# W5500_2.net
KiCad netlist of a schematic drawn in Altium Designer
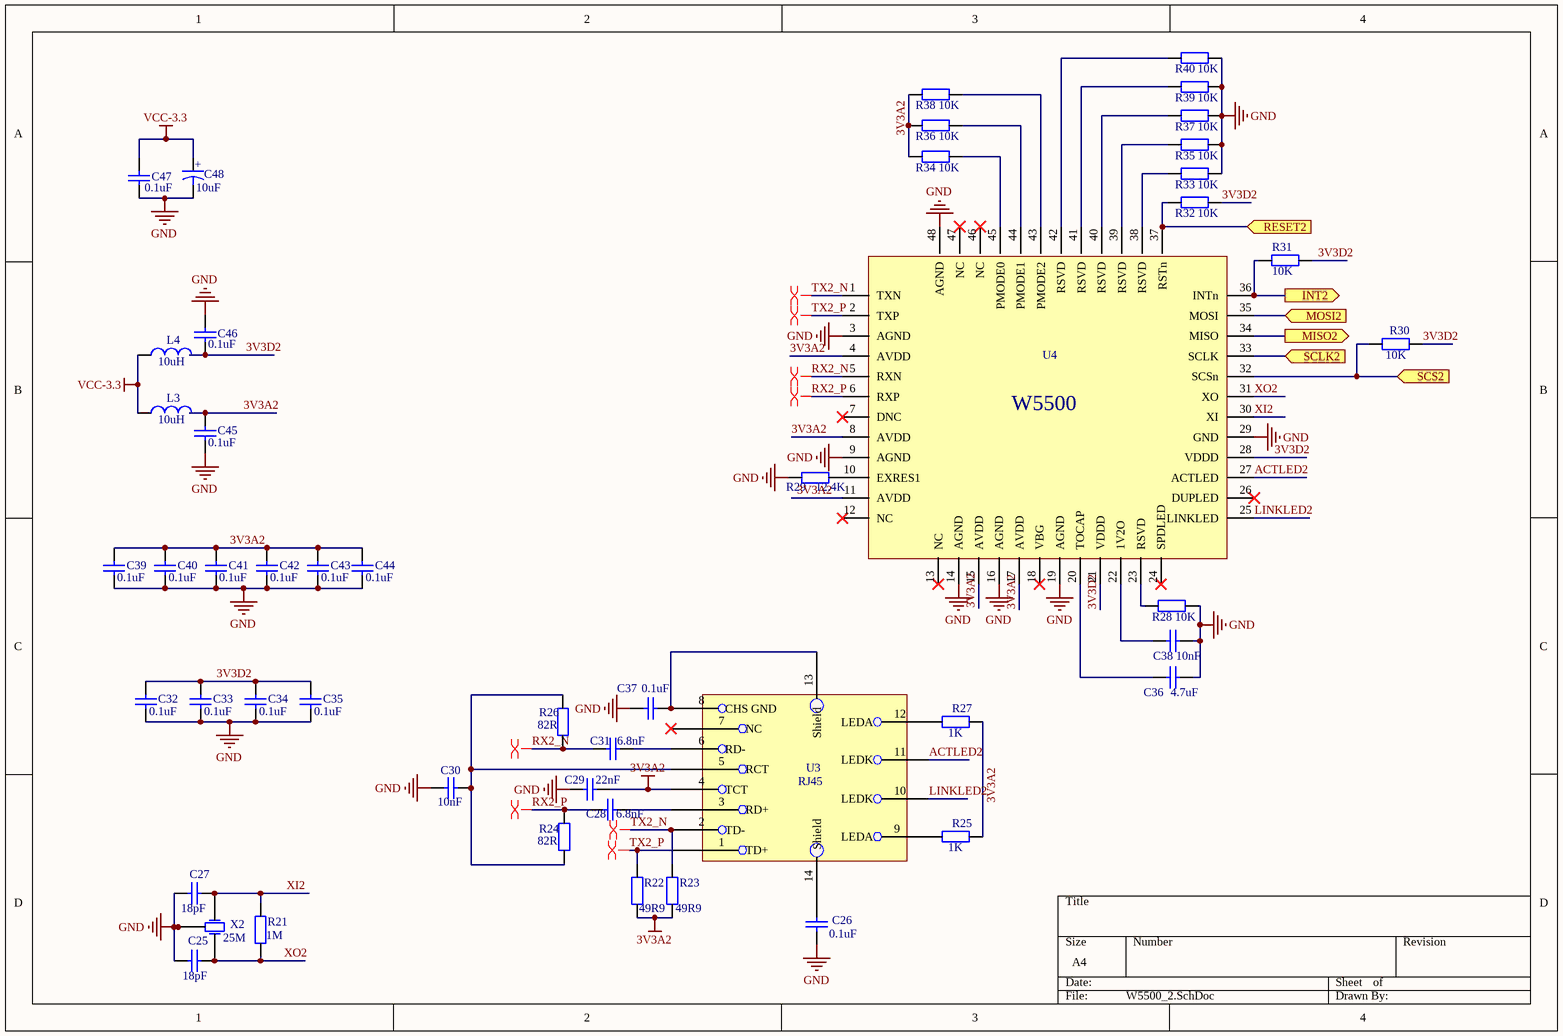
[diagram p0: W5500_2.SchDoc]

(export (version "E")
  (design (tool "Eeschema 10.0.6"))
  (components
    (comp (ref "C25")
      (value "18pF")
      (footprint "0603")
      (fields (field (name "Comment") "Capacitor-0603"))
      (libsource (lib "原理图库") (part "Capacitor-0603"))
    )
    (comp (ref "C26")
      (value "0.1uF")
      (footprint "0603")
      (fields (field (name "Comment") "Capacitor-0603"))
      (libsource (lib "原理图库") (part "Capacitor-0603"))
    )
    (comp (ref "C27")
      (value "18pF")
      (footprint "0603")
      (fields (field (name "Comment") "Capacitor-0603"))
      (libsource (lib "原理图库") (part "Capacitor-0603"))
    )
    (comp (ref "C28")
      (value "6.8nF")
      (footprint "0603")
      (fields (field (name "Comment") "Capacitor-0603"))
      (libsource (lib "原理图库") (part "Capacitor-0603"))
    )
    (comp (ref "C29")
      (value "22nF")
      (footprint "0603")
      (fields (field (name "Comment") "Capacitor-0603"))
      (libsource (lib "原理图库") (part "Capacitor-0603"))
    )
    (comp (ref "C30")
      (value "10nF")
      (footprint "0603")
      (fields (field (name "Comment") "Capacitor-0603"))
      (libsource (lib "原理图库") (part "Capacitor-0603"))
    )
    (comp (ref "C31")
      (value "6.8nF")
      (footprint "0603")
      (fields (field (name "Comment") "Capacitor-0603"))
      (libsource (lib "原理图库") (part "Capacitor-0603"))
    )
    (comp (ref "C32")
      (value "0.1uF")
      (footprint "0603")
      (fields (field (name "Comment") "Capacitor-0603"))
      (libsource (lib "原理图库") (part "Capacitor-0603"))
    )
    (comp (ref "C33")
      (value "0.1uF")
      (footprint "0603")
      (fields (field (name "Comment") "Capacitor-0603"))
      (libsource (lib "原理图库") (part "Capacitor-0603"))
    )
    (comp (ref "C34")
      (value "0.1uF")
      (footprint "0603")
      (fields (field (name "Comment") "Capacitor-0603"))
      (libsource (lib "原理图库") (part "Capacitor-0603"))
    )
    (comp (ref "C35")
      (value "0.1uF")
      (footprint "0603")
      (fields (field (name "Comment") "Capacitor-0603"))
      (libsource (lib "原理图库") (part "Capacitor-0603"))
    )
    (comp (ref "C36")
      (value "4.7uF")
      (footprint "0603")
      (fields (field (name "Comment") "Capacitor-0805"))
      (libsource (lib "原理图库") (part "Capacitor-0805"))
    )
    (comp (ref "C37")
      (value "0.1uF")
      (footprint "0603")
      (fields (field (name "Comment") "Capacitor-0603"))
      (libsource (lib "原理图库") (part "Capacitor-0603"))
    )
    (comp (ref "C38")
      (value "10nF")
      (footprint "0603")
      (fields (field (name "Comment") "Capacitor-0603"))
      (libsource (lib "原理图库") (part "Capacitor-0603"))
    )
    (comp (ref "C39")
      (value "0.1uF")
      (footprint "0603")
      (fields (field (name "Comment") "Capacitor-0603"))
      (libsource (lib "原理图库") (part "Capacitor-0603"))
    )
    (comp (ref "C40")
      (value "0.1uF")
      (footprint "0603")
      (fields (field (name "Comment") "Capacitor-0603"))
      (libsource (lib "原理图库") (part "Capacitor-0603"))
    )
    (comp (ref "C41")
      (value "0.1uF")
      (footprint "0603")
      (fields (field (name "Comment") "Capacitor-0603"))
      (libsource (lib "原理图库") (part "Capacitor-0603"))
    )
    (comp (ref "C42")
      (value "0.1uF")
      (footprint "0603")
      (fields (field (name "Comment") "Capacitor-0603"))
      (libsource (lib "原理图库") (part "Capacitor-0603"))
    )
    (comp (ref "C43")
      (value "0.1uF")
      (footprint "0603")
      (fields (field (name "Comment") "Capacitor-0603"))
      (libsource (lib "原理图库") (part "Capacitor-0603"))
    )
    (comp (ref "C44")
      (value "0.1uF")
      (footprint "0603")
      (fields (field (name "Comment") "Capacitor-0603"))
      (libsource (lib "原理图库") (part "Capacitor-0603"))
    )
    (comp (ref "C45")
      (value "0.1uF")
      (footprint "0603")
      (fields (field (name "Comment") "Capacitor-0603"))
      (libsource (lib "原理图库") (part "Capacitor-0603"))
    )
    (comp (ref "C46")
      (value "0.1uF")
      (footprint "0603")
      (fields (field (name "Comment") "Capacitor-0603"))
      (libsource (lib "原理图库") (part "Capacitor-0603"))
    )
    (comp (ref "C47")
      (value "0.1uF")
      (footprint "0603")
      (fields (field (name "Comment") "Capacitor-0603"))
      (libsource (lib "原理图库") (part "Capacitor-0603"))
    )
    (comp (ref "C48")
      (value "10uF")
      (footprint "钽电容1206（A3216）")
      (fields (field (name "ALTIUM_UNNAMED_1") "+") (field (name "Comment") "电解电容"))
      (libsource (lib "原理图库") (part "电解电容"))
    )
    (comp (ref "L3")
      (value "10uH")
      (footprint "0805")
      (fields (field (name "Comment") "Inductor"))
      (libsource (lib "原理图库") (part "Inductor"))
    )
    (comp (ref "L4")
      (value "10uH")
      (footprint "0805")
      (fields (field (name "Comment") "Inductor"))
      (libsource (lib "原理图库") (part "Inductor"))
    )
    (comp (ref "R21")
      (value "1M")
      (footprint "0603")
      (fields (field (name "Comment") "Resistor-0603"))
      (libsource (lib "") (part "Resistor-0603_1"))
    )
    (comp (ref "R22")
      (value "49R9")
      (footprint "0603")
      (fields (field (name "Comment") "Resistor-0603"))
      (libsource (lib "") (part "Resistor-0603_1"))
    )
    (comp (ref "R23")
      (value "49R9")
      (footprint "0603")
      (fields (field (name "Comment") "Resistor-0603"))
      (libsource (lib "") (part "Resistor-0603_1"))
    )
    (comp (ref "R24")
      (value "82R")
      (footprint "0603")
      (fields (field (name "Comment") "Resistor-0603"))
      (libsource (lib "") (part "Resistor-0603_1"))
    )
    (comp (ref "R25")
      (value "1K")
      (footprint "0603")
      (fields (field (name "Comment") "Resistor-0603"))
      (libsource (lib "") (part "Resistor-0603_2"))
    )
    (comp (ref "R26")
      (value "82R")
      (footprint "0603")
      (fields (field (name "Comment") "Resistor-0603"))
      (libsource (lib "") (part "Resistor-0603_1"))
    )
    (comp (ref "R27")
      (value "1K")
      (footprint "0603")
      (fields (field (name "Comment") "Resistor-0603"))
      (libsource (lib "") (part "Resistor-0603_2"))
    )
    (comp (ref "R28")
      (value "10K")
      (footprint "0603")
      (fields (field (name "Comment") "Resistor-0603"))
      (libsource (lib "原理图库") (part "Resistor-0603"))
    )
    (comp (ref "R29")
      (value "12.4K")
      (footprint "0603")
      (fields (field (name "Comment") "Resistor-0603"))
      (libsource (lib "原理图库") (part "Resistor-0603"))
    )
    (comp (ref "R30")
      (value "10K")
      (footprint "0603")
      (fields (field (name "Comment") "Resistor-0603"))
      (libsource (lib "") (part "Resistor-0603_2"))
    )
    (comp (ref "R31")
      (value "10K")
      (footprint "0603")
      (fields (field (name "Comment") "Resistor-0603"))
      (libsource (lib "") (part "Resistor-0603_2"))
    )
    (comp (ref "R32")
      (value "10K")
      (footprint "0603")
      (fields (field (name "Comment") "Resistor-0603"))
      (libsource (lib "原理图库") (part "Resistor-0603"))
    )
    (comp (ref "R33")
      (value "10K")
      (footprint "0603")
      (fields (field (name "Comment") "Resistor-0603"))
      (libsource (lib "原理图库") (part "Resistor-0603"))
    )
    (comp (ref "R34")
      (value "10K")
      (footprint "0603")
      (fields (field (name "Comment") "Resistor-0603"))
      (libsource (lib "原理图库") (part "Resistor-0603"))
    )
    (comp (ref "R35")
      (value "10K")
      (footprint "0603")
      (fields (field (name "Comment") "Resistor-0603"))
      (libsource (lib "原理图库") (part "Resistor-0603"))
    )
    (comp (ref "R36")
      (value "10K")
      (footprint "0603")
      (fields (field (name "Comment") "Resistor-0603"))
      (libsource (lib "原理图库") (part "Resistor-0603"))
    )
    (comp (ref "R37")
      (value "10K")
      (footprint "0603")
      (fields (field (name "Comment") "Resistor-0603"))
      (libsource (lib "原理图库") (part "Resistor-0603"))
    )
    (comp (ref "R38")
      (value "10K")
      (footprint "0603")
      (fields (field (name "Comment") "Resistor-0603"))
      (libsource (lib "原理图库") (part "Resistor-0603"))
    )
    (comp (ref "R39")
      (value "10K")
      (footprint "0603")
      (fields (field (name "Comment") "Resistor-0603"))
      (libsource (lib "原理图库") (part "Resistor-0603"))
    )
    (comp (ref "R40")
      (value "10K")
      (footprint "0603")
      (fields (field (name "Comment") "Resistor-0603"))
      (libsource (lib "原理图库") (part "Resistor-0603"))
    )
    (comp (ref "U3")
      (value "RJ45")
      (footprint "RJ45")
      (fields (field (name "NAME") "RJ45"))
      (libsource (lib "原理图库") (part "RJ45"))
    )
    (comp (ref "U4") (value "W5500") (footprint "W5500") (libsource (lib "原理图库") (part "W5500")))
    (comp (ref "X2")
      (value "25M")
      (footprint "3225无源晶振")
      (fields (field (name "Comment") "3225无源晶振"))
      (libsource (lib "原理图库") (part "3225无源晶振"))
    )
  )
  (nets
    (net (code "1") (name "/3V3D2") (class "Default")
      (node (ref "C32") (pin "1") (pinfunction "1_1") (pintype "passive"))
      (node (ref "C33") (pin "1") (pinfunction "1_1") (pintype "passive"))
      (node (ref "C34") (pin "1") (pinfunction "1_1") (pintype "passive"))
      (node (ref "C35") (pin "1") (pinfunction "1_1") (pintype "passive"))
      (node (ref "C46") (pin "1") (pinfunction "1_1") (pintype "passive"))
      (node (ref "L4") (pin "2") (pinfunction "2_2") (pintype "passive"))
      (node (ref "R30") (pin "2") (pinfunction "2_2") (pintype "passive"))
      (node (ref "R31") (pin "2") (pinfunction "2_2") (pintype "passive"))
      (node (ref "R32") (pin "1") (pinfunction "1_1") (pintype "passive"))
      (node (ref "U4") (pin "21") (pinfunction "VDDD_21") (pintype "passive"))
      (node (ref "U4") (pin "28") (pinfunction "VDDD_28") (pintype "passive"))
    )
    (net (code "2") (name "/ACTLED2") (class "Default")
      (node (ref "U3") (pin "11") (pinfunction "LEDK_11") (pintype "passive"))
      (node (ref "U4") (pin "27") (pinfunction "ACTLED_27") (pintype "passive"))
    )
    (net (code "3") (name "/INT2") (class "Default")
      (node (ref "R31") (pin "1") (pinfunction "1_1") (pintype "passive"))
      (node (ref "U4") (pin "36") (pinfunction "INTn_36") (pintype "passive"))
    )
    (net (code "4") (name "/LINKLED2") (class "Default")
      (node (ref "U3") (pin "10") (pinfunction "LEDK_10") (pintype "passive"))
      (node (ref "U4") (pin "25") (pinfunction "LINKLED_25") (pintype "passive"))
    )
    (net (code "5") (name "/MISO2") (class "Default")
      (node (ref "U4") (pin "34") (pinfunction "MISO_34") (pintype "passive"))
    )
    (net (code "6") (name "/MOSI2") (class "Default")
      (node (ref "U4") (pin "35") (pinfunction "MOSI_35") (pintype "passive"))
    )
    (net (code "7") (name "/RESET2") (class "Default")
      (node (ref "R32") (pin "2") (pinfunction "2_2") (pintype "passive"))
      (node (ref "U4") (pin "37") (pinfunction "RSTn_37") (pintype "passive"))
    )
    (net (code "8") (name "/RX2_N") (class "Default")
      (node (ref "C31") (pin "1") (pinfunction "1_1") (pintype "passive"))
      (node (ref "R26") (pin "2") (pinfunction "2_2") (pintype "passive"))
      (node (ref "U4") (pin "5") (pinfunction "RXN_5") (pintype "passive"))
    )
    (net (code "9") (name "/RX2_P") (class "Default")
      (node (ref "C28") (pin "1") (pinfunction "1_1") (pintype "passive"))
      (node (ref "R24") (pin "1") (pinfunction "1_1") (pintype "passive"))
      (node (ref "U4") (pin "6") (pinfunction "RXP_6") (pintype "passive"))
    )
    (net (code "10") (name "/SCLK2") (class "Default")
      (node (ref "U4") (pin "33") (pinfunction "SCLK_33") (pintype "passive"))
    )
    (net (code "11") (name "/SCS2") (class "Default")
      (node (ref "R30") (pin "1") (pinfunction "1_1") (pintype "passive"))
      (node (ref "U4") (pin "32") (pinfunction "SCSn_32") (pintype "passive"))
    )
    (net (code "12") (name "/TX2_N") (class "Default")
      (node (ref "R23") (pin "1") (pinfunction "1_1") (pintype "passive"))
      (node (ref "U3") (pin "2") (pinfunction "TD-_2") (pintype "passive"))
      (node (ref "U4") (pin "1") (pinfunction "TXN_1") (pintype "passive"))
    )
    (net (code "13") (name "/TX2_P") (class "Default")
      (node (ref "R22") (pin "1") (pinfunction "1_1") (pintype "passive"))
      (node (ref "U3") (pin "1") (pinfunction "TD+_1") (pintype "passive"))
      (node (ref "U4") (pin "2") (pinfunction "TXP_2") (pintype "passive"))
    )
    (net (code "14") (name "/XI2") (class "Default")
      (node (ref "C27") (pin "2") (pinfunction "2_2") (pintype "passive"))
      (node (ref "R21") (pin "1") (pinfunction "1_1") (pintype "passive"))
      (node (ref "U4") (pin "30") (pinfunction "XI_30") (pintype "passive"))
      (node (ref "X2") (pin "1") (pinfunction "OSC1_1") (pintype "passive"))
    )
    (net (code "15") (name "/XO2") (class "Default")
      (node (ref "C25") (pin "2") (pinfunction "2_2") (pintype "passive"))
      (node (ref "R21") (pin "2") (pinfunction "2_2") (pintype "passive"))
      (node (ref "U4") (pin "31") (pinfunction "XO_31") (pintype "passive"))
      (node (ref "X2") (pin "3") (pinfunction "OSC2_3") (pintype "passive"))
    )
    (net (code "16") (name "3V3A2") (class "Default")
      (node (ref "C29") (pin "2") (pinfunction "2_2") (pintype "passive"))
      (node (ref "C39") (pin "1") (pinfunction "1_1") (pintype "passive"))
      (node (ref "C40") (pin "1") (pinfunction "1_1") (pintype "passive"))
      (node (ref "C41") (pin "1") (pinfunction "1_1") (pintype "passive"))
      (node (ref "C42") (pin "1") (pinfunction "1_1") (pintype "passive"))
      (node (ref "C43") (pin "1") (pinfunction "1_1") (pintype "passive"))
      (node (ref "C44") (pin "1") (pinfunction "1_1") (pintype "passive"))
      (node (ref "C45") (pin "1") (pinfunction "1_1") (pintype "passive"))
      (node (ref "L3") (pin "2") (pinfunction "2_2") (pintype "passive"))
      (node (ref "R22") (pin "2") (pinfunction "2_2") (pintype "passive"))
      (node (ref "R23") (pin "2") (pinfunction "2_2") (pintype "passive"))
      (node (ref "R25") (pin "2") (pinfunction "2_2") (pintype "passive"))
      (node (ref "R27") (pin "2") (pinfunction "2_2") (pintype "passive"))
      (node (ref "R34") (pin "2") (pinfunction "2_2") (pintype "passive"))
      (node (ref "R36") (pin "2") (pinfunction "2_2") (pintype "passive"))
      (node (ref "R38") (pin "2") (pinfunction "2_2") (pintype "passive"))
      (node (ref "U3") (pin "4") (pinfunction "TCT_4") (pintype "passive"))
      (node (ref "U4") (pin "11") (pinfunction "AVDD_11") (pintype "passive"))
      (node (ref "U4") (pin "15") (pinfunction "AVDD_15") (pintype "passive"))
      (node (ref "U4") (pin "17") (pinfunction "AVDD_17") (pintype "passive"))
      (node (ref "U4") (pin "4") (pinfunction "AVDD_4") (pintype "passive"))
      (node (ref "U4") (pin "8") (pinfunction "AVDD_8") (pintype "passive"))
    )
    (net (code "17") (name "GND") (class "Default")
      (node (ref "C25") (pin "1") (pinfunction "1_1") (pintype "passive"))
      (node (ref "C26") (pin "2") (pinfunction "2_2") (pintype "passive"))
      (node (ref "C27") (pin "1") (pinfunction "1_1") (pintype "passive"))
      (node (ref "C29") (pin "1") (pinfunction "1_1") (pintype "passive"))
      (node (ref "C30") (pin "1") (pinfunction "1_1") (pintype "passive"))
      (node (ref "C32") (pin "2") (pinfunction "2_2") (pintype "passive"))
      (node (ref "C33") (pin "2") (pinfunction "2_2") (pintype "passive"))
      (node (ref "C34") (pin "2") (pinfunction "2_2") (pintype "passive"))
      (node (ref "C35") (pin "2") (pinfunction "2_2") (pintype "passive"))
      (node (ref "C36") (pin "2") (pinfunction "2_2") (pintype "passive"))
      (node (ref "C37") (pin "2") (pinfunction "2_2") (pintype "passive"))
      (node (ref "C38") (pin "1") (pinfunction "1_1") (pintype "passive"))
      (node (ref "C39") (pin "2") (pinfunction "2_2") (pintype "passive"))
      (node (ref "C40") (pin "2") (pinfunction "2_2") (pintype "passive"))
      (node (ref "C41") (pin "2") (pinfunction "2_2") (pintype "passive"))
      (node (ref "C42") (pin "2") (pinfunction "2_2") (pintype "passive"))
      (node (ref "C43") (pin "2") (pinfunction "2_2") (pintype "passive"))
      (node (ref "C44") (pin "2") (pinfunction "2_2") (pintype "passive"))
      (node (ref "C45") (pin "2") (pinfunction "2_2") (pintype "passive"))
      (node (ref "C46") (pin "2") (pinfunction "2_2") (pintype "passive"))
      (node (ref "C47") (pin "1") (pinfunction "1_1") (pintype "passive"))
      (node (ref "C48") (pin "1") (pinfunction "1_1") (pintype "passive"))
      (node (ref "R28") (pin "1") (pinfunction "1_1") (pintype "passive"))
      (node (ref "R29") (pin "2") (pinfunction "2_2") (pintype "passive"))
      (node (ref "R33") (pin "1") (pinfunction "1_1") (pintype "passive"))
      (node (ref "R35") (pin "1") (pinfunction "1_1") (pintype "passive"))
      (node (ref "R37") (pin "1") (pinfunction "1_1") (pintype "passive"))
      (node (ref "R39") (pin "1") (pinfunction "1_1") (pintype "passive"))
      (node (ref "R40") (pin "1") (pinfunction "1_1") (pintype "passive"))
      (node (ref "U4") (pin "14") (pinfunction "AGND_14") (pintype "passive"))
      (node (ref "U4") (pin "16") (pinfunction "AGND_16") (pintype "passive"))
      (node (ref "U4") (pin "19") (pinfunction "AGND_19") (pintype "passive"))
      (node (ref "U4") (pin "29") (pinfunction "GND_29") (pintype "passive"))
      (node (ref "U4") (pin "3") (pinfunction "AGND_3") (pintype "passive"))
      (node (ref "U4") (pin "48") (pinfunction "AGND_48") (pintype "passive"))
      (node (ref "U4") (pin "9") (pinfunction "AGND_9") (pintype "passive"))
      (node (ref "X2") (pin "2") (pinfunction "GND_2") (pintype "passive"))
      (node (ref "X2") (pin "4") (pinfunction "GND_4") (pintype "passive"))
    )
    (net (code "18") (name "Net-(C26-Pad1)") (class "Default")
      (node (ref "C26") (pin "1") (pinfunction "1_1") (pintype "passive"))
      (node (ref "U3") (pin "14") (pinfunction "Shield_14") (pintype "passive"))
    )
    (net (code "19") (name "Net-(R25-Pad1)") (class "Default")
      (node (ref "R25") (pin "1") (pinfunction "1_1") (pintype "passive"))
      (node (ref "U3") (pin "9") (pinfunction "LEDA_9") (pintype "passive"))
    )
    (net (code "20") (name "Net-(R27-Pad1)") (class "Default")
      (node (ref "R27") (pin "1") (pinfunction "1_1") (pintype "passive"))
      (node (ref "U3") (pin "12") (pinfunction "LEDA_12") (pintype "passive"))
    )
    (net (code "21") (name "Net-(R28-Pad2)") (class "Default")
      (node (ref "R28") (pin "2") (pinfunction "2_2") (pintype "passive"))
      (node (ref "U4") (pin "23") (pinfunction "RSVD_23") (pintype "passive"))
    )
    (net (code "22") (name "Net-(R33-Pad2)") (class "Default")
      (node (ref "R33") (pin "2") (pinfunction "2_2") (pintype "passive"))
      (node (ref "U4") (pin "38") (pinfunction "RSVD_38") (pintype "passive"))
    )
    (net (code "23") (name "Net-(R35-Pad2)") (class "Default")
      (node (ref "R35") (pin "2") (pinfunction "2_2") (pintype "passive"))
      (node (ref "U4") (pin "39") (pinfunction "RSVD_39") (pintype "passive"))
    )
    (net (code "24") (name "Net-(R37-Pad2)") (class "Default")
      (node (ref "R37") (pin "2") (pinfunction "2_2") (pintype "passive"))
      (node (ref "U4") (pin "40") (pinfunction "RSVD_40") (pintype "passive"))
    )
    (net (code "25") (name "Net-(R39-Pad2)") (class "Default")
      (node (ref "R39") (pin "2") (pinfunction "2_2") (pintype "passive"))
      (node (ref "U4") (pin "41") (pinfunction "RSVD_41") (pintype "passive"))
    )
    (net (code "26") (name "Net-(R40-Pad2)") (class "Default")
      (node (ref "R40") (pin "2") (pinfunction "2_2") (pintype "passive"))
      (node (ref "U4") (pin "42") (pinfunction "RSVD_42") (pintype "passive"))
    )
    (net (code "27") (name "Net-(U3-CHS_GND)") (class "Default")
      (node (ref "C37") (pin "1") (pinfunction "1_1") (pintype "passive"))
      (node (ref "U3") (pin "13") (pinfunction "Shield_13") (pintype "passive"))
      (node (ref "U3") (pin "8") (pinfunction "CHS_GND_8") (pintype "passive"))
    )
    (net (code "28") (name "Net-(U3-RCT)") (class "Default")
      (node (ref "C30") (pin "2") (pinfunction "2_2") (pintype "passive"))
      (node (ref "R24") (pin "2") (pinfunction "2_2") (pintype "passive"))
      (node (ref "R26") (pin "1") (pinfunction "1_1") (pintype "passive"))
      (node (ref "U3") (pin "5") (pinfunction "RCT_5") (pintype "passive"))
    )
    (net (code "29") (name "Net-(U3-RD+)") (class "Default")
      (node (ref "C28") (pin "2") (pinfunction "2_2") (pintype "passive"))
      (node (ref "U3") (pin "3") (pinfunction "RD+_3") (pintype "passive"))
    )
    (net (code "30") (name "Net-(U3-RD-)") (class "Default")
      (node (ref "C31") (pin "2") (pinfunction "2_2") (pintype "passive"))
      (node (ref "U3") (pin "6") (pinfunction "RD-_6") (pintype "passive"))
    )
    (net (code "31") (name "Net-(U4-1V2O)") (class "Default")
      (node (ref "C38") (pin "2") (pinfunction "2_2") (pintype "passive"))
      (node (ref "U4") (pin "22") (pinfunction "1V2O_22") (pintype "passive"))
    )
    (net (code "32") (name "Net-(U4-EXRES1)") (class "Default")
      (node (ref "R29") (pin "1") (pinfunction "1_1") (pintype "passive"))
      (node (ref "U4") (pin "10") (pinfunction "EXRES1_10") (pintype "passive"))
    )
    (net (code "33") (name "Net-(U4-PMODE0)") (class "Default")
      (node (ref "R34") (pin "1") (pinfunction "1_1") (pintype "passive"))
      (node (ref "U4") (pin "45") (pinfunction "PMODE0_45") (pintype "passive"))
    )
    (net (code "34") (name "Net-(U4-PMODE1)") (class "Default")
      (node (ref "R36") (pin "1") (pinfunction "1_1") (pintype "passive"))
      (node (ref "U4") (pin "44") (pinfunction "PMODE1_44") (pintype "passive"))
    )
    (net (code "35") (name "Net-(U4-PMODE2)") (class "Default")
      (node (ref "R38") (pin "1") (pinfunction "1_1") (pintype "passive"))
      (node (ref "U4") (pin "43") (pinfunction "PMODE2_43") (pintype "passive"))
    )
    (net (code "36") (name "Net-(U4-TOCAP)") (class "Default")
      (node (ref "C36") (pin "1") (pinfunction "1_1") (pintype "passive"))
      (node (ref "U4") (pin "20") (pinfunction "TOCAP_20") (pintype "passive"))
    )
    (net (code "37") (name "VCC-3.3") (class "Default")
      (node (ref "C47") (pin "2") (pinfunction "2_2") (pintype "passive"))
      (node (ref "C48") (pin "2") (pinfunction "2_2") (pintype "passive"))
      (node (ref "L3") (pin "1") (pinfunction "1_1") (pintype "passive"))
      (node (ref "L4") (pin "1") (pinfunction "1_1") (pintype "passive"))
    )
    (net (code "38") (name "unconnected-(U3-NC-Pad7)") (class "Default")
      (node (ref "U3") (pin "7") (pinfunction "NC_7") (pintype "passive+no_connect"))
    )
    (net (code "39") (name "unconnected-(U4-DNC-Pad7)") (class "Default")
      (node (ref "U4") (pin "7") (pinfunction "DNC_7") (pintype "passive+no_connect"))
    )
    (net (code "40") (name "unconnected-(U4-DUPLED-Pad26)") (class "Default")
      (node (ref "U4") (pin "26") (pinfunction "DUPLED_26") (pintype "passive+no_connect"))
    )
    (net (code "41") (name "unconnected-(U4-NC-Pad12)") (class "Default")
      (node (ref "U4") (pin "12") (pinfunction "NC_12") (pintype "passive+no_connect"))
    )
    (net (code "42") (name "unconnected-(U4-NC-Pad13)") (class "Default")
      (node (ref "U4") (pin "13") (pinfunction "NC_13") (pintype "passive+no_connect"))
    )
    (net (code "43") (name "unconnected-(U4-NC-Pad46)") (class "Default")
      (node (ref "U4") (pin "46") (pinfunction "NC_46") (pintype "passive+no_connect"))
    )
    (net (code "44") (name "unconnected-(U4-NC-Pad47)") (class "Default")
      (node (ref "U4") (pin "47") (pinfunction "NC_47") (pintype "passive+no_connect"))
    )
    (net (code "45") (name "unconnected-(U4-SPDLED-Pad24)") (class "Default")
      (node (ref "U4") (pin "24") (pinfunction "SPDLED_24") (pintype "passive+no_connect"))
    )
    (net (code "46") (name "unconnected-(U4-VBG-Pad18)") (class "Default")
      (node (ref "U4") (pin "18") (pinfunction "VBG_18") (pintype "passive+no_connect"))
    )
  )
)
